# ESP-12F-BREAK.net
KiCad netlist of a schematic drawn in EAGLE
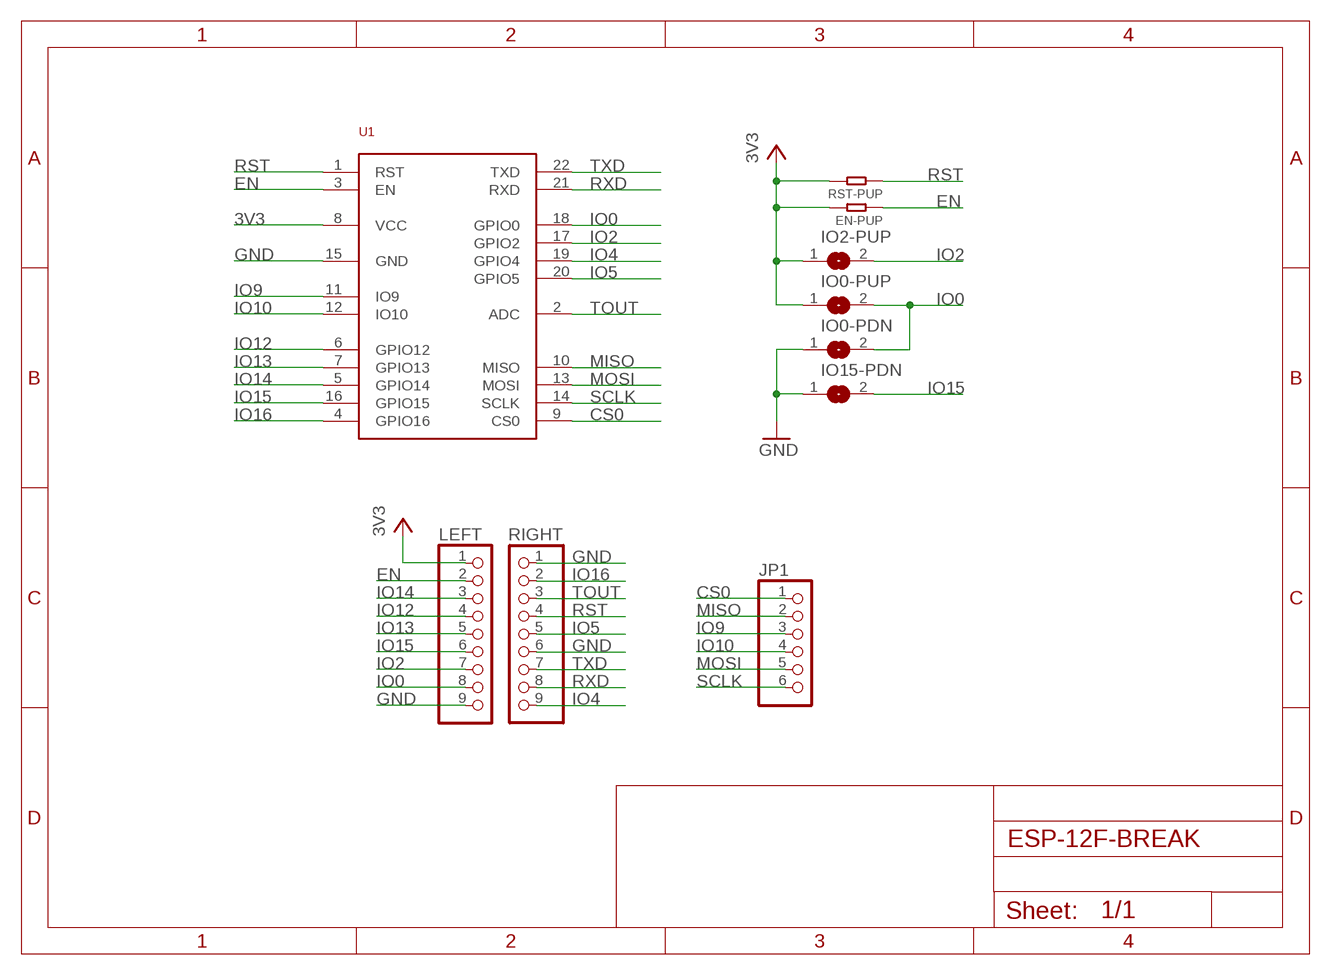
[diagram p0: schematic, sheet 1]

(export (version "E")
  (design (tool "Eeschema 10.0.6"))
  (components
    (comp (ref "EN-PUP")
      (value "10K")
      (footprint "eagle-import:R0805")
      (fields (field (name "MPN") "RC0805FR-0710KL"))
      (libsource (lib "eagle-import") (part "SMD-RES-10K-1%-1/8W(0805)"))
    )
    (comp (ref "IO0-PDN")
      (value "SJ")
      (footprint "eagle-import:SJ")
      (libsource (lib "eagle-import") (part "SJ"))
    )
    (comp (ref "IO0-PUP")
      (value "SJ")
      (footprint "eagle-import:SJ")
      (libsource (lib "eagle-import") (part "SJ"))
    )
    (comp (ref "IO2-PUP")
      (value "SJ")
      (footprint "eagle-import:SJ")
      (libsource (lib "eagle-import") (part "SJ"))
    )
    (comp (ref "IO15-PDN")
      (value "SJ")
      (footprint "eagle-import:SJ")
      (libsource (lib "eagle-import") (part "SJ"))
    )
    (comp (ref "JP1")
      (value "PINHD-1X6")
      (footprint "eagle-import:1X06")
      (libsource (lib "eagle-import") (part "PINHD-1X6"))
    )
    (comp (ref "LEFT")
      (value "PINHD-1X9")
      (footprint "eagle-import:1X09")
      (libsource (lib "eagle-import") (part "PINHD-1X9"))
    )
    (comp (ref "RIGHT")
      (value "PINHD-1X9")
      (footprint "eagle-import:1X09")
      (libsource (lib "eagle-import") (part "PINHD-1X9"))
    )
    (comp (ref "RST-PUP")
      (value "10K")
      (footprint "eagle-import:R0805")
      (fields (field (name "MPN") "RC0805FR-0710KL"))
      (libsource (lib "eagle-import") (part "SMD-RES-10K-1%-1/8W(0805)"))
    )
    (comp (ref "U1")
      (value "ESP-12F")
      (footprint "eagle-import:ESP-12F")
      (libsource (lib "eagle-import") (part "ESP-12F"))
    )
  )
  (nets
    (net (code "1") (name "/CS0") (class "Default")
      (node (ref "JP1") (pin "1") (pinfunction "1_1") (pintype "passive"))
      (node (ref "U1") (pin "9") (pinfunction "CS0_9") (pintype "bidirectional"))
    )
    (net (code "2") (name "/EN") (class "Default")
      (node (ref "EN-PUP") (pin "1") (pinfunction "1_1") (pintype "passive"))
      (node (ref "LEFT") (pin "2") (pinfunction "2_2") (pintype "passive"))
      (node (ref "U1") (pin "3") (pinfunction "EN_3") (pintype "bidirectional"))
    )
    (net (code "3") (name "/IO0") (class "Default")
      (node (ref "IO0-PDN") (pin "2") (pinfunction "2_2") (pintype "passive"))
      (node (ref "IO0-PUP") (pin "2") (pinfunction "2_2") (pintype "passive"))
      (node (ref "LEFT") (pin "8") (pinfunction "8_8") (pintype "passive"))
      (node (ref "U1") (pin "18") (pinfunction "GPIO0_18") (pintype "bidirectional"))
    )
    (net (code "4") (name "/IO2") (class "Default")
      (node (ref "IO2-PUP") (pin "2") (pinfunction "2_2") (pintype "passive"))
      (node (ref "LEFT") (pin "7") (pinfunction "7_7") (pintype "passive"))
      (node (ref "U1") (pin "17") (pinfunction "GPIO2_17") (pintype "bidirectional"))
    )
    (net (code "5") (name "/IO4") (class "Default")
      (node (ref "RIGHT") (pin "9") (pinfunction "9_9") (pintype "passive"))
      (node (ref "U1") (pin "19") (pinfunction "GPIO4_19") (pintype "bidirectional"))
    )
    (net (code "6") (name "/IO5") (class "Default")
      (node (ref "RIGHT") (pin "5") (pinfunction "5_5") (pintype "passive"))
      (node (ref "U1") (pin "20") (pinfunction "GPIO5_20") (pintype "bidirectional"))
    )
    (net (code "7") (name "/IO9") (class "Default")
      (node (ref "JP1") (pin "3") (pinfunction "3_3") (pintype "passive"))
      (node (ref "U1") (pin "11") (pinfunction "IO9_11") (pintype "bidirectional"))
    )
    (net (code "8") (name "/IO10") (class "Default")
      (node (ref "JP1") (pin "4") (pinfunction "4_4") (pintype "passive"))
      (node (ref "U1") (pin "12") (pinfunction "IO10_12") (pintype "bidirectional"))
    )
    (net (code "9") (name "/IO12") (class "Default")
      (node (ref "LEFT") (pin "4") (pinfunction "4_4") (pintype "passive"))
      (node (ref "U1") (pin "6") (pinfunction "GPIO12_6") (pintype "bidirectional"))
    )
    (net (code "10") (name "/IO13") (class "Default")
      (node (ref "LEFT") (pin "5") (pinfunction "5_5") (pintype "passive"))
      (node (ref "U1") (pin "7") (pinfunction "GPIO13_7") (pintype "bidirectional"))
    )
    (net (code "11") (name "/IO14") (class "Default")
      (node (ref "LEFT") (pin "3") (pinfunction "3_3") (pintype "passive"))
      (node (ref "U1") (pin "5") (pinfunction "GPIO14_5") (pintype "bidirectional"))
    )
    (net (code "12") (name "/IO15") (class "Default")
      (node (ref "IO15-PDN") (pin "2") (pinfunction "2_2") (pintype "passive"))
      (node (ref "LEFT") (pin "6") (pinfunction "6_6") (pintype "passive"))
      (node (ref "U1") (pin "16") (pinfunction "GPIO15_16") (pintype "bidirectional"))
    )
    (net (code "13") (name "/IO16") (class "Default")
      (node (ref "RIGHT") (pin "2") (pinfunction "2_2") (pintype "passive"))
      (node (ref "U1") (pin "4") (pinfunction "GPIO16_4") (pintype "bidirectional"))
    )
    (net (code "14") (name "/MISO") (class "Default")
      (node (ref "JP1") (pin "2") (pinfunction "2_2") (pintype "passive"))
      (node (ref "U1") (pin "10") (pinfunction "MISO_10") (pintype "bidirectional"))
    )
    (net (code "15") (name "/MOSI") (class "Default")
      (node (ref "JP1") (pin "5") (pinfunction "5_5") (pintype "passive"))
      (node (ref "U1") (pin "13") (pinfunction "MOSI_13") (pintype "bidirectional"))
    )
    (net (code "16") (name "/RST") (class "Default")
      (node (ref "RIGHT") (pin "4") (pinfunction "4_4") (pintype "passive"))
      (node (ref "RST-PUP") (pin "1") (pinfunction "1_1") (pintype "passive"))
      (node (ref "U1") (pin "1") (pinfunction "RST_1") (pintype "bidirectional"))
    )
    (net (code "17") (name "/RXD") (class "Default")
      (node (ref "RIGHT") (pin "8") (pinfunction "8_8") (pintype "passive"))
      (node (ref "U1") (pin "21") (pinfunction "RXD_21") (pintype "bidirectional"))
    )
    (net (code "18") (name "/SCLK") (class "Default")
      (node (ref "JP1") (pin "6") (pinfunction "6_6") (pintype "passive"))
      (node (ref "U1") (pin "14") (pinfunction "SCLK_14") (pintype "bidirectional"))
    )
    (net (code "19") (name "/TOUT") (class "Default")
      (node (ref "RIGHT") (pin "3") (pinfunction "3_3") (pintype "passive"))
      (node (ref "U1") (pin "2") (pinfunction "ADC_2") (pintype "bidirectional"))
    )
    (net (code "20") (name "/TXD") (class "Default")
      (node (ref "RIGHT") (pin "7") (pinfunction "7_7") (pintype "passive"))
      (node (ref "U1") (pin "22") (pinfunction "TXD_22") (pintype "bidirectional"))
    )
    (net (code "21") (name "3V3") (class "Default")
      (node (ref "EN-PUP") (pin "2") (pinfunction "2_2") (pintype "passive"))
      (node (ref "IO0-PUP") (pin "1") (pinfunction "1_1") (pintype "passive"))
      (node (ref "IO2-PUP") (pin "1") (pinfunction "1_1") (pintype "passive"))
      (node (ref "LEFT") (pin "1") (pinfunction "1_1") (pintype "passive"))
      (node (ref "RST-PUP") (pin "2") (pinfunction "2_2") (pintype "passive"))
      (node (ref "U1") (pin "8") (pinfunction "VCC_8") (pintype "bidirectional"))
    )
    (net (code "22") (name "GND") (class "Default")
      (node (ref "IO0-PDN") (pin "1") (pinfunction "1_1") (pintype "passive"))
      (node (ref "IO15-PDN") (pin "1") (pinfunction "1_1") (pintype "passive"))
      (node (ref "LEFT") (pin "9") (pinfunction "9_9") (pintype "passive"))
      (node (ref "RIGHT") (pin "1") (pinfunction "1_1") (pintype "passive"))
      (node (ref "RIGHT") (pin "6") (pinfunction "6_6") (pintype "passive"))
      (node (ref "U1") (pin "15") (pinfunction "GND_15") (pintype "bidirectional"))
    )
  )
)
